# sensorHubRev7.net
KiCad netlist of a schematic drawn in EAGLE
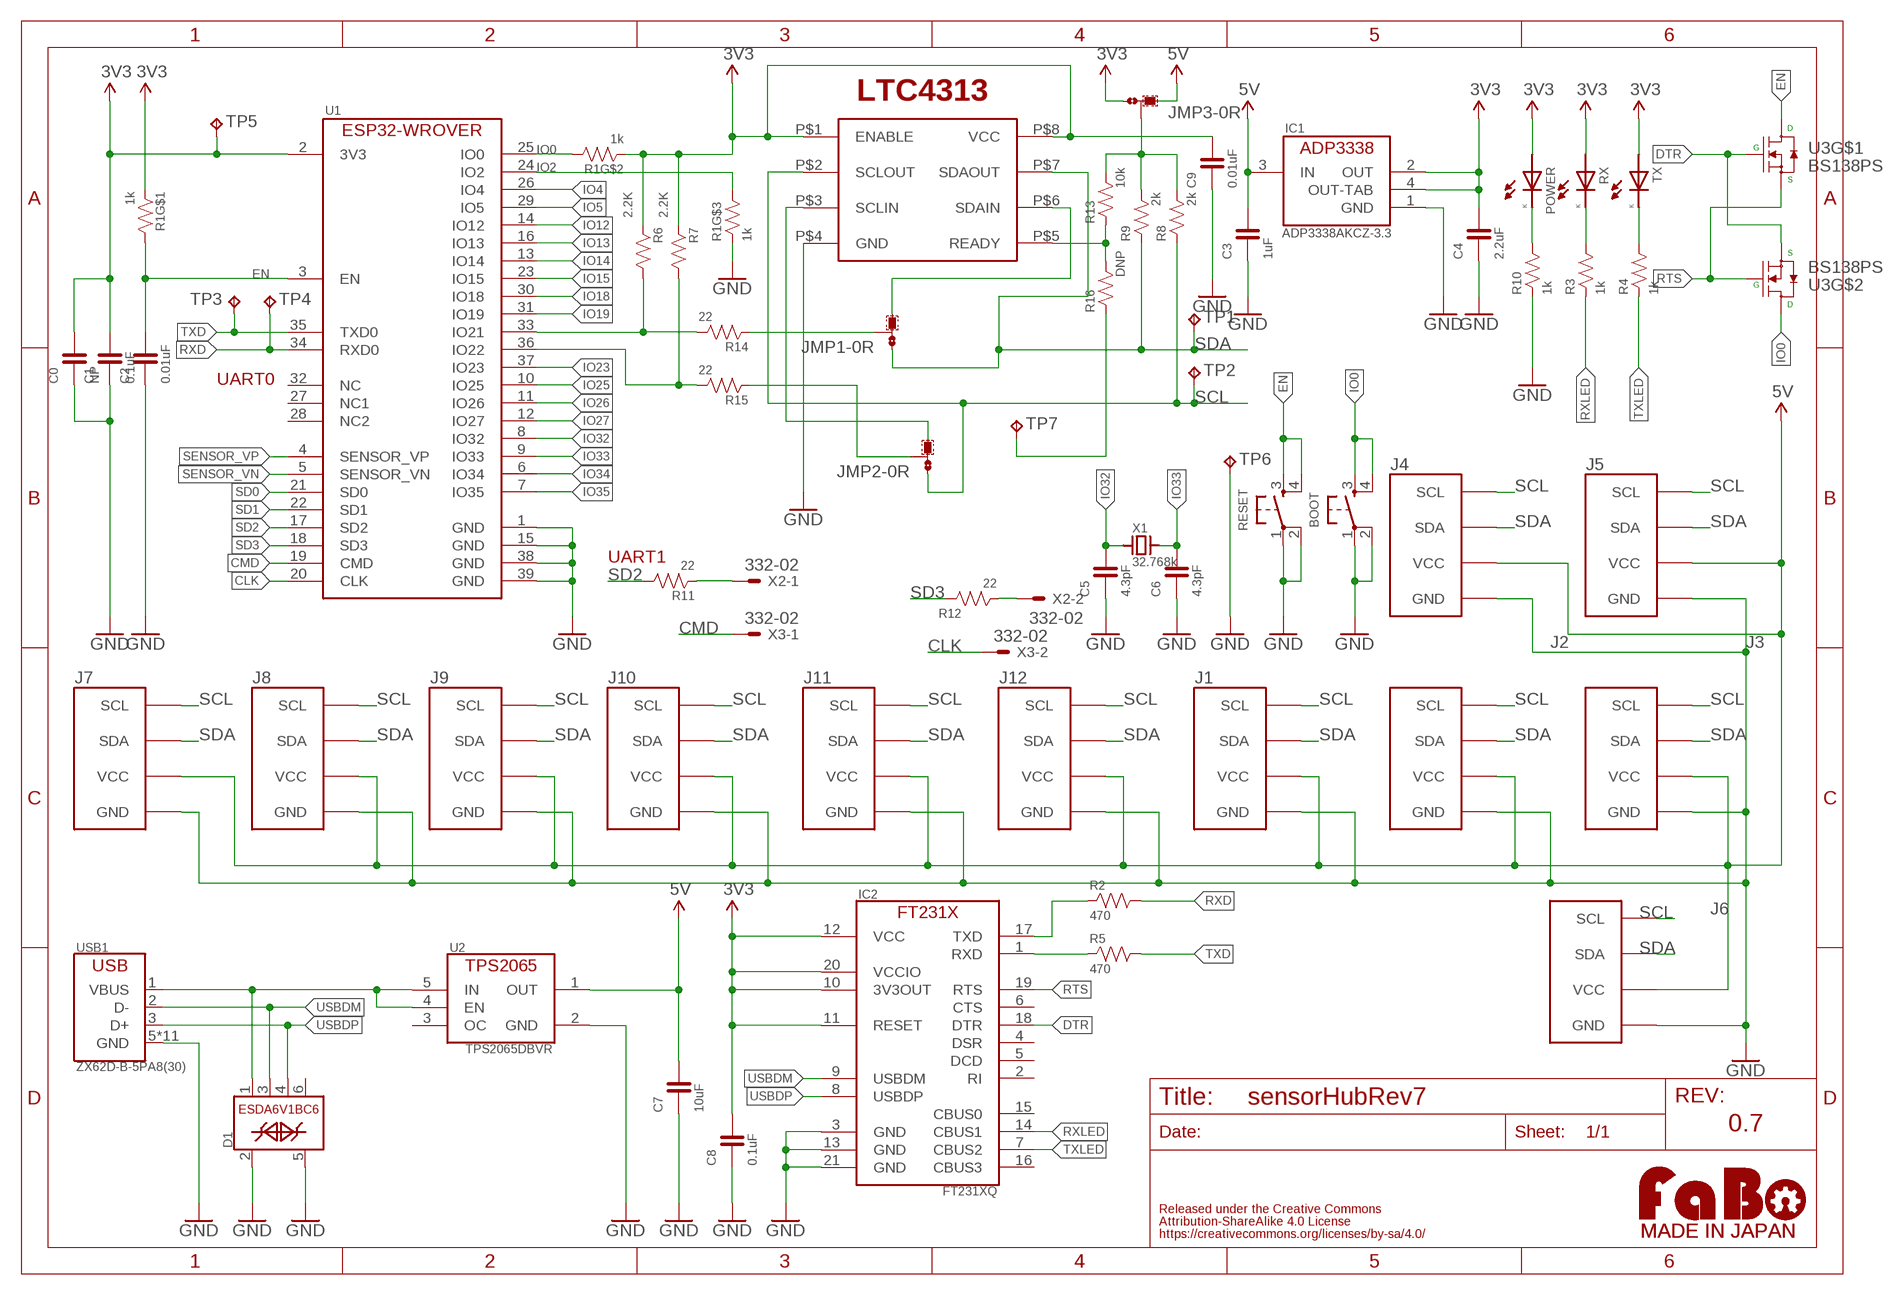
[diagram p0: schematic, sheet 1]

(export (version "E")
  (design (tool "Eeschema 10.0.6"))
  (components
    (comp (ref "BOOT")
      (value "TACTILE-KMR2")
      (footprint "eagle-import:KMR2-TACT")
      (libsource (lib "eagle-import") (part "TACTILE-KMR2"))
    )
    (comp (ref "C0")
      (value "NP")
      (footprint "eagle-import:MULTIPAD0603")
      (libsource (lib "eagle-import") (part "CAPACITOR-M"))
    )
    (comp (ref "C1")
      (value "0.1uF")
      (footprint "eagle-import:EIA0603")
      (libsource (lib "eagle-import") (part "CAPACITOR-0603"))
    )
    (comp (ref "C2")
      (value "0.01uF")
      (footprint "eagle-import:EIA0603")
      (libsource (lib "eagle-import") (part "CAPACITOR-0603"))
    )
    (comp (ref "C3")
      (value "1uF")
      (footprint "eagle-import:EIA0603")
      (libsource (lib "eagle-import") (part "CAPACITOR-0603"))
    )
    (comp (ref "C4")
      (value "2.2uF")
      (footprint "eagle-import:EIA0603")
      (libsource (lib "eagle-import") (part "CAPACITOR-0603"))
    )
    (comp (ref "C5")
      (value "4.3pF")
      (footprint "eagle-import:EIA0603")
      (libsource (lib "eagle-import") (part "CAPACITOR-0603"))
    )
    (comp (ref "C6")
      (value "4.3pF")
      (footprint "eagle-import:EIA0603")
      (libsource (lib "eagle-import") (part "CAPACITOR-0603"))
    )
    (comp (ref "C7")
      (value "10uF")
      (footprint "eagle-import:EIA0603")
      (libsource (lib "eagle-import") (part "CAPACITOR-0603"))
    )
    (comp (ref "C8")
      (value "0.1uF")
      (footprint "eagle-import:EIA0603")
      (libsource (lib "eagle-import") (part "CAPACITOR-0603"))
    )
    (comp (ref "C9")
      (value "0.01uF")
      (footprint "eagle-import:EIA0603")
      (libsource (lib "eagle-import") (part "CAPACITOR-0603"))
    )
    (comp (ref "D1")
      (value "ESDA6V1BC6")
      (footprint "eagle-import:SOT-23-6L")
      (libsource (lib "eagle-import") (part "ESDA6V1BC6"))
    )
    (comp (ref "IC1")
      (value "ADP3338AKCZ-3.3")
      (footprint "eagle-import:SOT-223-KC3")
      (libsource (lib "eagle-import") (part "ADP3338AKCZ"))
    )
    (comp (ref "IC2")
      (value "FT231XQ")
      (footprint "eagle-import:QFN-20")
      (libsource (lib "eagle-import") (part "FT231XQ"))
    )
    (comp (ref "J1")
      (value "FABO_BRICK_I2C-S04B-PASK-2")
      (footprint "eagle-import:FABO_BRICK_I2C_S04B-PASK-2")
      (libsource (lib "eagle-import") (part "FABO_BRICK_I2C-S04B-PASK-2"))
    )
    (comp (ref "J2")
      (value "FABO_BRICK_I2C-S04B-PASK-2")
      (footprint "eagle-import:FABO_BRICK_I2C_S04B-PASK-2")
      (libsource (lib "eagle-import") (part "FABO_BRICK_I2C-S04B-PASK-2"))
    )
    (comp (ref "J3")
      (value "FABO_BRICK_I2C-S04B-PASK-2")
      (footprint "eagle-import:FABO_BRICK_I2C_S04B-PASK-2")
      (libsource (lib "eagle-import") (part "FABO_BRICK_I2C-S04B-PASK-2"))
    )
    (comp (ref "J4")
      (value "FABO_BRICK_I2C-S04B-PASK-2")
      (footprint "eagle-import:FABO_BRICK_I2C_S04B-PASK-2")
      (libsource (lib "eagle-import") (part "FABO_BRICK_I2C-S04B-PASK-2"))
    )
    (comp (ref "J5")
      (value "FABO_BRICK_I2C-S04B-PASK-2")
      (footprint "eagle-import:FABO_BRICK_I2C_S04B-PASK-2")
      (libsource (lib "eagle-import") (part "FABO_BRICK_I2C-S04B-PASK-2"))
    )
    (comp (ref "J6")
      (value "FABO_BRICK_I2C-S04B-PASK-2")
      (footprint "eagle-import:FABO_BRICK_I2C_S04B-PASK-2")
      (libsource (lib "eagle-import") (part "FABO_BRICK_I2C-S04B-PASK-2"))
    )
    (comp (ref "J7")
      (value "FABO_BRICK_I2C-S04B-PASK-2")
      (footprint "eagle-import:FABO_BRICK_I2C_S04B-PASK-2")
      (libsource (lib "eagle-import") (part "FABO_BRICK_I2C-S04B-PASK-2"))
    )
    (comp (ref "J8")
      (value "FABO_BRICK_I2C-S04B-PASK-2")
      (footprint "eagle-import:FABO_BRICK_I2C_S04B-PASK-2")
      (libsource (lib "eagle-import") (part "FABO_BRICK_I2C-S04B-PASK-2"))
    )
    (comp (ref "J9")
      (value "FABO_BRICK_I2C-S04B-PASK-2")
      (footprint "eagle-import:FABO_BRICK_I2C_S04B-PASK-2")
      (libsource (lib "eagle-import") (part "FABO_BRICK_I2C-S04B-PASK-2"))
    )
    (comp (ref "J10")
      (value "FABO_BRICK_I2C-S04B-PASK-2")
      (footprint "eagle-import:FABO_BRICK_I2C_S04B-PASK-2")
      (libsource (lib "eagle-import") (part "FABO_BRICK_I2C-S04B-PASK-2"))
    )
    (comp (ref "J11")
      (value "FABO_BRICK_I2C-S04B-PASK-2")
      (footprint "eagle-import:FABO_BRICK_I2C_S04B-PASK-2")
      (libsource (lib "eagle-import") (part "FABO_BRICK_I2C-S04B-PASK-2"))
    )
    (comp (ref "J12")
      (value "FABO_BRICK_I2C-S04B-PASK-2")
      (footprint "eagle-import:FABO_BRICK_I2C_S04B-PASK-2")
      (libsource (lib "eagle-import") (part "FABO_BRICK_I2C-S04B-PASK-2"))
    )
    (comp (ref "JMP1")
      (value "0R-JUMPA")
      (footprint "eagle-import:A0R-JMP")
      (libsource (lib "eagle-import") (part "0R-JUMPA"))
    )
    (comp (ref "JMP2")
      (value "0R-JUMPA")
      (footprint "eagle-import:A0R-JMP")
      (libsource (lib "eagle-import") (part "0R-JUMPA"))
    )
    (comp (ref "JMP3")
      (value "0R-JUMPB")
      (footprint "eagle-import:B0R-JMP")
      (libsource (lib "eagle-import") (part "0R-JUMPB"))
    )
    (comp (ref "LOGO1")
      (value "LOGO_FABO-M_BOTTOM")
      (footprint "eagle-import:LOGO_FABO_M_BOTTOM")
      (libsource (lib "eagle-import") (part "LOGO_FABO-M_BOTTOM"))
    )
    (comp (ref "POWER")
      (value "LED-0603")
      (footprint "eagle-import:LED_0603")
      (libsource (lib "eagle-import") (part "LED-0603"))
    )
    (comp (ref "R1")
      (value "1k")
      (footprint "eagle-import:EXBV8V")
      (libsource (lib "eagle-import") (part "RESISTOR_ARRAY"))
    )
    (comp (ref "R2")
      (value "470")
      (footprint "eagle-import:EIA0603")
      (libsource (lib "eagle-import") (part "RESISTOR-0603"))
    )
    (comp (ref "R3")
      (value "1k")
      (footprint "eagle-import:EIA0603")
      (libsource (lib "eagle-import") (part "RESISTOR-0603"))
    )
    (comp (ref "R4")
      (value "1k")
      (footprint "eagle-import:EIA0603")
      (libsource (lib "eagle-import") (part "RESISTOR-0603"))
    )
    (comp (ref "R5")
      (value "470")
      (footprint "eagle-import:EIA0603")
      (libsource (lib "eagle-import") (part "RESISTOR-0603"))
    )
    (comp (ref "R6")
      (value "2.2K")
      (footprint "eagle-import:EIA0603")
      (libsource (lib "eagle-import") (part "RESISTOR-0603"))
    )
    (comp (ref "R7")
      (value "2.2K")
      (footprint "eagle-import:EIA0603")
      (libsource (lib "eagle-import") (part "RESISTOR-0603"))
    )
    (comp (ref "R8")
      (value "2k")
      (footprint "eagle-import:EIA0603")
      (libsource (lib "eagle-import") (part "RESISTOR-0603"))
    )
    (comp (ref "R9")
      (value "2k")
      (footprint "eagle-import:EIA0603")
      (libsource (lib "eagle-import") (part "RESISTOR-0603"))
    )
    (comp (ref "R10")
      (value "1k")
      (footprint "eagle-import:EIA0603")
      (libsource (lib "eagle-import") (part "RESISTOR-0603"))
    )
    (comp (ref "R11")
      (value "22")
      (footprint "eagle-import:EIA0603")
      (libsource (lib "eagle-import") (part "RESISTOR-0603"))
    )
    (comp (ref "R12")
      (value "22")
      (footprint "eagle-import:EIA0603")
      (libsource (lib "eagle-import") (part "RESISTOR-0603"))
    )
    (comp (ref "R13")
      (value "10k")
      (footprint "eagle-import:EIA0603")
      (libsource (lib "eagle-import") (part "RESISTOR-0603"))
    )
    (comp (ref "R14")
      (value "22")
      (footprint "eagle-import:EIA0603")
      (libsource (lib "eagle-import") (part "RESISTOR-0603"))
    )
    (comp (ref "R15")
      (value "22")
      (footprint "eagle-import:EIA0603")
      (libsource (lib "eagle-import") (part "RESISTOR-0603"))
    )
    (comp (ref "R16")
      (value "DNP")
      (footprint "eagle-import:EIA0603")
      (libsource (lib "eagle-import") (part "RESISTOR-0603"))
    )
    (comp (ref "RESET")
      (value "TACTILE-KMR2")
      (footprint "eagle-import:KMR2-TACT")
      (libsource (lib "eagle-import") (part "TACTILE-KMR2"))
    )
    (comp (ref "RX")
      (value "LED-0603")
      (footprint "eagle-import:LED_0603")
      (libsource (lib "eagle-import") (part "LED-0603"))
    )
    (comp (ref "TP1")
      (value "TPB1,27")
      (footprint "eagle-import:B1,27")
      (libsource (lib "eagle-import") (part "TPB1,27"))
    )
    (comp (ref "TP2")
      (value "TPB1,27")
      (footprint "eagle-import:B1,27")
      (libsource (lib "eagle-import") (part "TPB1,27"))
    )
    (comp (ref "TP3")
      (value "TPB1,27")
      (footprint "eagle-import:B1,27")
      (libsource (lib "eagle-import") (part "TPB1,27"))
    )
    (comp (ref "TP4")
      (value "TPB1,27")
      (footprint "eagle-import:B1,27")
      (libsource (lib "eagle-import") (part "TPB1,27"))
    )
    (comp (ref "TP5")
      (value "TPB1,27")
      (footprint "eagle-import:B1,27")
      (libsource (lib "eagle-import") (part "TPB1,27"))
    )
    (comp (ref "TP6")
      (value "TPB1,27")
      (footprint "eagle-import:B1,27")
      (libsource (lib "eagle-import") (part "TPB1,27"))
    )
    (comp (ref "TP7")
      (value "TPB1,27")
      (footprint "eagle-import:B1,27")
      (libsource (lib "eagle-import") (part "TPB1,27"))
    )
    (comp (ref "TX")
      (value "LED-0603")
      (footprint "eagle-import:LED_0603")
      (libsource (lib "eagle-import") (part "LED-0603"))
    )
    (comp (ref "U1")
      (value "ESP32-WROVER-B")
      (footprint "eagle-import:ESP32-WROVER-B")
      (libsource (lib "eagle-import") (part "ESP32-WROVER-B"))
    )
    (comp (ref "U2")
      (value "TPS2065DBVR")
      (footprint "eagle-import:SOT-23-5")
      (libsource (lib "eagle-import") (part "TPS2065DBV"))
    )
    (comp (ref "U3")
      (value "BS138PS")
      (footprint "eagle-import:SOT-363")
      (libsource (lib "eagle-import") (part "BS138PS"))
    )
    (comp (ref "U5")
      (value "LTC4313")
      (footprint "eagle-import:LTC4313")
      (libsource (lib "eagle-import") (part "LTC4313"))
    )
    (comp (ref "USB1")
      (value "ZX62D-B-5PA8(30)")
      (footprint "eagle-import:ZX62D-B-5PA8")
      (libsource (lib "eagle-import") (part "USB-ZX62D"))
    )
    (comp (ref "X1")
      (value "32.768k")
      (footprint "eagle-import:ABS07")
      (libsource (lib "eagle-import") (part "CRYSTAL-ABS07"))
    )
    (comp (ref "X2")
      (value "332-02")
      (footprint "eagle-import:332-02")
      (libsource (lib "eagle-import") (part "332-02"))
    )
    (comp (ref "X3")
      (value "332-02")
      (footprint "eagle-import:332-02")
      (libsource (lib "eagle-import") (part "332-02"))
    )
  )
  (nets
    (net (code "1") (name "/IO2") (class "Default")
      (node (ref "R1") (pin "6") (pinfunction "2_6") (pintype "bidirectional"))
      (node (ref "U1") (pin "24") (pinfunction "IO2_24") (pintype "bidirectional"))
    )
    (net (code "2") (name "/SCL") (class "Default")
      (node (ref "J1") (pin "SCL") (pinfunction "SCL_SCL") (pintype "bidirectional"))
      (node (ref "J10") (pin "SCL") (pinfunction "SCL_SCL") (pintype "bidirectional"))
      (node (ref "J11") (pin "SCL") (pinfunction "SCL_SCL") (pintype "bidirectional"))
      (node (ref "J12") (pin "SCL") (pinfunction "SCL_SCL") (pintype "bidirectional"))
      (node (ref "J2") (pin "SCL") (pinfunction "SCL_SCL") (pintype "bidirectional"))
      (node (ref "J3") (pin "SCL") (pinfunction "SCL_SCL") (pintype "bidirectional"))
      (node (ref "J4") (pin "SCL") (pinfunction "SCL_SCL") (pintype "bidirectional"))
      (node (ref "J5") (pin "SCL") (pinfunction "SCL_SCL") (pintype "bidirectional"))
      (node (ref "J6") (pin "SCL") (pinfunction "SCL_SCL") (pintype "bidirectional"))
      (node (ref "J7") (pin "SCL") (pinfunction "SCL_SCL") (pintype "bidirectional"))
      (node (ref "J8") (pin "SCL") (pinfunction "SCL_SCL") (pintype "bidirectional"))
      (node (ref "J9") (pin "SCL") (pinfunction "SCL_SCL") (pintype "bidirectional"))
      (node (ref "JMP2") (pin "1") (pinfunction "1_1") (pintype "passive"))
      (node (ref "R8") (pin "1") (pinfunction "1_1") (pintype "bidirectional"))
      (node (ref "TP2") (pin "TP") (pinfunction "TP_TP") (pintype "input"))
      (node (ref "U5") (pin "P$2") (pinfunction "SCLOUT_P$2") (pintype "bidirectional"))
    )
    (net (code "3") (name "/SDA") (class "Default")
      (node (ref "J1") (pin "SDA") (pinfunction "SDA_SDA") (pintype "bidirectional"))
      (node (ref "J10") (pin "SDA") (pinfunction "SDA_SDA") (pintype "bidirectional"))
      (node (ref "J11") (pin "SDA") (pinfunction "SDA_SDA") (pintype "bidirectional"))
      (node (ref "J12") (pin "SDA") (pinfunction "SDA_SDA") (pintype "bidirectional"))
      (node (ref "J2") (pin "SDA") (pinfunction "SDA_SDA") (pintype "bidirectional"))
      (node (ref "J3") (pin "SDA") (pinfunction "SDA_SDA") (pintype "bidirectional"))
      (node (ref "J4") (pin "SDA") (pinfunction "SDA_SDA") (pintype "bidirectional"))
      (node (ref "J5") (pin "SDA") (pinfunction "SDA_SDA") (pintype "bidirectional"))
      (node (ref "J6") (pin "SDA") (pinfunction "SDA_SDA") (pintype "bidirectional"))
      (node (ref "J7") (pin "SDA") (pinfunction "SDA_SDA") (pintype "bidirectional"))
      (node (ref "J8") (pin "SDA") (pinfunction "SDA_SDA") (pintype "bidirectional"))
      (node (ref "J9") (pin "SDA") (pinfunction "SDA_SDA") (pintype "bidirectional"))
      (node (ref "JMP1") (pin "1") (pinfunction "1_1") (pintype "passive"))
      (node (ref "R9") (pin "1") (pinfunction "1_1") (pintype "bidirectional"))
      (node (ref "TP1") (pin "TP") (pinfunction "TP_TP") (pintype "input"))
      (node (ref "U5") (pin "P$7") (pinfunction "SDAOUT_P$7") (pintype "bidirectional"))
    )
    (net (code "4") (name "3V3") (class "Default")
      (node (ref "C0") (pin "2") (pinfunction "2_2") (pintype "passive"))
      (node (ref "C1") (pin "2") (pinfunction "2_2") (pintype "passive"))
      (node (ref "C4") (pin "2") (pinfunction "2_2") (pintype "passive"))
      (node (ref "C8") (pin "2") (pinfunction "2_2") (pintype "passive"))
      (node (ref "C9") (pin "2") (pinfunction "2_2") (pintype "passive"))
      (node (ref "IC1") (pin "2") (pinfunction "OUT_2") (pintype "bidirectional"))
      (node (ref "IC1") (pin "4") (pinfunction "OUT-TAB_4") (pintype "bidirectional"))
      (node (ref "IC2") (pin "10") (pinfunction "3V3OUT_10") (pintype "bidirectional"))
      (node (ref "IC2") (pin "11") (pinfunction "RESET_11") (pintype "bidirectional"))
      (node (ref "IC2") (pin "12") (pinfunction "VCC_12") (pintype "bidirectional"))
      (node (ref "IC2") (pin "20") (pinfunction "VCCIO_20") (pintype "bidirectional"))
      (node (ref "JMP3") (pin "3") (pinfunction "3_3") (pintype "passive"))
      (node (ref "POWER") (pin "A") (pinfunction "ANODE_A") (pintype "passive"))
      (node (ref "R1") (pin "1") (pinfunction "1_1") (pintype "bidirectional"))
      (node (ref "R1") (pin "2") (pinfunction "1_2") (pintype "bidirectional"))
      (node (ref "R6") (pin "1") (pinfunction "1_1") (pintype "bidirectional"))
      (node (ref "R7") (pin "1") (pinfunction "1_1") (pintype "bidirectional"))
      (node (ref "RX") (pin "A") (pinfunction "ANODE_A") (pintype "passive"))
      (node (ref "TP5") (pin "TP") (pinfunction "TP_TP") (pintype "input"))
      (node (ref "TX") (pin "A") (pinfunction "ANODE_A") (pintype "passive"))
      (node (ref "U1") (pin "2") (pinfunction "3V3_2") (pintype "bidirectional"))
      (node (ref "U5") (pin "P$1") (pinfunction "ENABLE_P$1") (pintype "bidirectional"))
      (node (ref "U5") (pin "P$8") (pinfunction "VCC_P$8") (pintype "bidirectional"))
    )
    (net (code "5") (name "5V") (class "Default")
      (node (ref "C3") (pin "2") (pinfunction "2_2") (pintype "passive"))
      (node (ref "C7") (pin "2") (pinfunction "2_2") (pintype "passive"))
      (node (ref "IC1") (pin "3") (pinfunction "IN_3") (pintype "bidirectional"))
      (node (ref "J1") (pin "VCC") (pinfunction "VCC_VCC") (pintype "bidirectional"))
      (node (ref "J10") (pin "VCC") (pinfunction "VCC_VCC") (pintype "bidirectional"))
      (node (ref "J11") (pin "VCC") (pinfunction "VCC_VCC") (pintype "bidirectional"))
      (node (ref "J12") (pin "VCC") (pinfunction "VCC_VCC") (pintype "bidirectional"))
      (node (ref "J2") (pin "VCC") (pinfunction "VCC_VCC") (pintype "bidirectional"))
      (node (ref "J3") (pin "VCC") (pinfunction "VCC_VCC") (pintype "bidirectional"))
      (node (ref "J4") (pin "VCC") (pinfunction "VCC_VCC") (pintype "bidirectional"))
      (node (ref "J5") (pin "VCC") (pinfunction "VCC_VCC") (pintype "bidirectional"))
      (node (ref "J6") (pin "VCC") (pinfunction "VCC_VCC") (pintype "bidirectional"))
      (node (ref "J7") (pin "VCC") (pinfunction "VCC_VCC") (pintype "bidirectional"))
      (node (ref "J8") (pin "VCC") (pinfunction "VCC_VCC") (pintype "bidirectional"))
      (node (ref "J9") (pin "VCC") (pinfunction "VCC_VCC") (pintype "bidirectional"))
      (node (ref "JMP3") (pin "1") (pinfunction "1_1") (pintype "passive"))
      (node (ref "U2") (pin "1") (pinfunction "OUT_1") (pintype "bidirectional"))
    )
    (net (code "6") (name "CLK") (class "Default")
      (node (ref "U1") (pin "20") (pinfunction "CLK_20") (pintype "bidirectional"))
      (node (ref "X3") (pin "2") (pinfunction "S_2") (pintype "passive"))
    )
    (net (code "7") (name "CMD") (class "Default")
      (node (ref "U1") (pin "19") (pinfunction "CMD_19") (pintype "bidirectional"))
      (node (ref "X3") (pin "1") (pinfunction "S_1") (pintype "passive"))
    )
    (net (code "8") (name "DTR") (class "Default")
      (node (ref "IC2") (pin "18") (pinfunction "DTR_18") (pintype "bidirectional"))
      (node (ref "U3") (pin "2") (pinfunction "G_2") (pintype "passive"))
      (node (ref "U3") (pin "4") (pinfunction "S_4") (pintype "passive"))
    )
    (net (code "9") (name "EN") (class "Default")
      (node (ref "C2") (pin "2") (pinfunction "2_2") (pintype "passive"))
      (node (ref "R1") (pin "8") (pinfunction "2_8") (pintype "bidirectional"))
      (node (ref "RESET") (pin "3") (pinfunction "3_3") (pintype "passive"))
      (node (ref "RESET") (pin "4") (pinfunction "4_4") (pintype "passive"))
      (node (ref "U1") (pin "3") (pinfunction "EN_3") (pintype "bidirectional"))
      (node (ref "U3") (pin "6") (pinfunction "D_6") (pintype "passive"))
    )
    (net (code "10") (name "GND") (class "Default")
      (node (ref "BOOT") (pin "1") (pinfunction "1_1") (pintype "passive"))
      (node (ref "BOOT") (pin "2") (pinfunction "2_2") (pintype "passive"))
      (node (ref "C0") (pin "1") (pinfunction "1_1") (pintype "passive"))
      (node (ref "C1") (pin "1") (pinfunction "1_1") (pintype "passive"))
      (node (ref "C2") (pin "1") (pinfunction "1_1") (pintype "passive"))
      (node (ref "C3") (pin "1") (pinfunction "1_1") (pintype "passive"))
      (node (ref "C4") (pin "1") (pinfunction "1_1") (pintype "passive"))
      (node (ref "C5") (pin "1") (pinfunction "1_1") (pintype "passive"))
      (node (ref "C6") (pin "1") (pinfunction "1_1") (pintype "passive"))
      (node (ref "C7") (pin "1") (pinfunction "1_1") (pintype "passive"))
      (node (ref "C8") (pin "1") (pinfunction "1_1") (pintype "passive"))
      (node (ref "C9") (pin "1") (pinfunction "1_1") (pintype "passive"))
      (node (ref "D1") (pin "2") (pinfunction "2_2") (pintype "bidirectional"))
      (node (ref "D1") (pin "5") (pinfunction "5_5") (pintype "bidirectional"))
      (node (ref "IC1") (pin "1") (pinfunction "GND_1") (pintype "bidirectional"))
      (node (ref "IC2") (pin "13") (pinfunction "GND_13") (pintype "bidirectional"))
      (node (ref "IC2") (pin "21") (pinfunction "GND_21") (pintype "bidirectional"))
      (node (ref "IC2") (pin "3") (pinfunction "GND_3") (pintype "bidirectional"))
      (node (ref "J1") (pin "GND") (pinfunction "GND_GND") (pintype "bidirectional"))
      (node (ref "J10") (pin "GND") (pinfunction "GND_GND") (pintype "bidirectional"))
      (node (ref "J11") (pin "GND") (pinfunction "GND_GND") (pintype "bidirectional"))
      (node (ref "J12") (pin "GND") (pinfunction "GND_GND") (pintype "bidirectional"))
      (node (ref "J2") (pin "GND") (pinfunction "GND_GND") (pintype "bidirectional"))
      (node (ref "J3") (pin "GND") (pinfunction "GND_GND") (pintype "bidirectional"))
      (node (ref "J4") (pin "GND") (pinfunction "GND_GND") (pintype "bidirectional"))
      (node (ref "J5") (pin "GND") (pinfunction "GND_GND") (pintype "bidirectional"))
      (node (ref "J6") (pin "GND") (pinfunction "GND_GND") (pintype "bidirectional"))
      (node (ref "J7") (pin "GND") (pinfunction "GND_GND") (pintype "bidirectional"))
      (node (ref "J8") (pin "GND") (pinfunction "GND_GND") (pintype "bidirectional"))
      (node (ref "J9") (pin "GND") (pinfunction "GND_GND") (pintype "bidirectional"))
      (node (ref "R1") (pin "3") (pinfunction "1_3") (pintype "bidirectional"))
      (node (ref "R10") (pin "1") (pinfunction "1_1") (pintype "bidirectional"))
      (node (ref "RESET") (pin "1") (pinfunction "1_1") (pintype "passive"))
      (node (ref "RESET") (pin "2") (pinfunction "2_2") (pintype "passive"))
      (node (ref "TP6") (pin "TP") (pinfunction "TP_TP") (pintype "input"))
      (node (ref "U1") (pin "1") (pinfunction "GND_1") (pintype "bidirectional"))
      (node (ref "U1") (pin "15") (pinfunction "GND_15") (pintype "bidirectional"))
      (node (ref "U1") (pin "38") (pinfunction "GND_38") (pintype "bidirectional"))
      (node (ref "U1") (pin "39") (pinfunction "GND_39") (pintype "bidirectional"))
      (node (ref "U2") (pin "2") (pinfunction "GND_2") (pintype "bidirectional"))
      (node (ref "U5") (pin "P$4") (pinfunction "GND_P$4") (pintype "bidirectional"))
      (node (ref "USB1") (pin "5") (pinfunction "GND_5") (pintype "bidirectional"))
      (node (ref "USB1") (pin "B1") (pinfunction "GND_B1") (pintype "bidirectional"))
      (node (ref "USB1") (pin "B2") (pinfunction "GND_B2") (pintype "bidirectional"))
      (node (ref "USB1") (pin "B3") (pinfunction "GND_B3") (pintype "bidirectional"))
      (node (ref "USB1") (pin "B4") (pinfunction "GND_B4") (pintype "bidirectional"))
      (node (ref "USB1") (pin "T1") (pinfunction "GND_T1") (pintype "bidirectional"))
      (node (ref "USB1") (pin "T2") (pinfunction "GND_T2") (pintype "bidirectional"))
      (node (ref "USB1") (pin "T3") (pinfunction "GND_T3") (pintype "bidirectional"))
      (node (ref "USB1") (pin "T4") (pinfunction "GND_T4") (pintype "bidirectional"))
      (node (ref "USB1") (pin "T5") (pinfunction "GND_T5") (pintype "bidirectional"))
      (node (ref "USB1") (pin "T6") (pinfunction "GND_T6") (pintype "bidirectional"))
    )
    (net (code "11") (name "IO0") (class "Default")
      (node (ref "BOOT") (pin "3") (pinfunction "3_3") (pintype "passive"))
      (node (ref "BOOT") (pin "4") (pinfunction "4_4") (pintype "passive"))
      (node (ref "R1") (pin "7") (pinfunction "2_7") (pintype "bidirectional"))
      (node (ref "U1") (pin "25") (pinfunction "IO0_25") (pintype "bidirectional"))
      (node (ref "U3") (pin "3") (pinfunction "D_3") (pintype "passive"))
    )
    (net (code "12") (name "IO4") (class "Default")
      (node (ref "U1") (pin "26") (pinfunction "IO4_26") (pintype "bidirectional"))
    )
    (net (code "13") (name "IO5") (class "Default")
      (node (ref "U1") (pin "29") (pinfunction "IO5_29") (pintype "bidirectional"))
    )
    (net (code "14") (name "IO12") (class "Default")
      (node (ref "U1") (pin "14") (pinfunction "IO12_14") (pintype "bidirectional"))
    )
    (net (code "15") (name "IO13") (class "Default")
      (node (ref "U1") (pin "16") (pinfunction "IO13_16") (pintype "bidirectional"))
    )
    (net (code "16") (name "IO14") (class "Default")
      (node (ref "U1") (pin "13") (pinfunction "IO14_13") (pintype "bidirectional"))
    )
    (net (code "17") (name "IO15") (class "Default")
      (node (ref "U1") (pin "23") (pinfunction "IO15_23") (pintype "bidirectional"))
    )
    (net (code "18") (name "IO18") (class "Default")
      (node (ref "U1") (pin "30") (pinfunction "IO18_30") (pintype "bidirectional"))
    )
    (net (code "19") (name "IO19") (class "Default")
      (node (ref "U1") (pin "31") (pinfunction "IO19_31") (pintype "bidirectional"))
    )
    (net (code "20") (name "IO23") (class "Default")
      (node (ref "U1") (pin "37") (pinfunction "IO23_37") (pintype "bidirectional"))
    )
    (net (code "21") (name "IO25") (class "Default")
      (node (ref "U1") (pin "10") (pinfunction "IO25_10") (pintype "bidirectional"))
    )
    (net (code "22") (name "IO26") (class "Default")
      (node (ref "U1") (pin "11") (pinfunction "IO26_11") (pintype "bidirectional"))
    )
    (net (code "23") (name "IO27") (class "Default")
      (node (ref "U1") (pin "12") (pinfunction "IO27_12") (pintype "bidirectional"))
    )
    (net (code "24") (name "IO32") (class "Default")
      (node (ref "C5") (pin "2") (pinfunction "2_2") (pintype "passive"))
      (node (ref "U1") (pin "8") (pinfunction "IO32_8") (pintype "bidirectional"))
      (node (ref "X1") (pin "1") (pinfunction "P$1_1") (pintype "bidirectional"))
    )
    (net (code "25") (name "IO33") (class "Default")
      (node (ref "C6") (pin "2") (pinfunction "2_2") (pintype "passive"))
      (node (ref "U1") (pin "9") (pinfunction "IO33_9") (pintype "bidirectional"))
      (node (ref "X1") (pin "2") (pinfunction "P$2_2") (pintype "bidirectional"))
    )
    (net (code "26") (name "IO34") (class "Default")
      (node (ref "U1") (pin "6") (pinfunction "IO34_6") (pintype "bidirectional"))
    )
    (net (code "27") (name "IO35") (class "Default")
      (node (ref "U1") (pin "7") (pinfunction "IO35_7") (pintype "bidirectional"))
    )
    (net (code "28") (name "Net-(IC2-RXD)") (class "Default")
      (node (ref "IC2") (pin "1") (pinfunction "RXD_1") (pintype "bidirectional"))
      (node (ref "R5") (pin "1") (pinfunction "1_1") (pintype "bidirectional"))
    )
    (net (code "29") (name "Net-(IC2-TXD)") (class "Default")
      (node (ref "IC2") (pin "17") (pinfunction "TXD_17") (pintype "bidirectional"))
      (node (ref "R2") (pin "1") (pinfunction "1_1") (pintype "bidirectional"))
    )
    (net (code "30") (name "Net-(JMP1-Pad2)") (class "Default")
      (node (ref "JMP1") (pin "2") (pinfunction "2_2") (pintype "passive"))
      (node (ref "R14") (pin "1") (pinfunction "1_1") (pintype "bidirectional"))
    )
    (net (code "31") (name "Net-(JMP2-Pad2)") (class "Default")
      (node (ref "JMP2") (pin "2") (pinfunction "2_2") (pintype "passive"))
      (node (ref "R15") (pin "1") (pinfunction "1_1") (pintype "bidirectional"))
    )
    (net (code "32") (name "Net-(JMP3-Pad2)") (class "Default")
      (node (ref "JMP3") (pin "2") (pinfunction "2_2") (pintype "passive"))
      (node (ref "R13") (pin "2") (pinfunction "2_2") (pintype "bidirectional"))
      (node (ref "R8") (pin "2") (pinfunction "2_2") (pintype "bidirectional"))
      (node (ref "R9") (pin "2") (pinfunction "2_2") (pintype "bidirectional"))
    )
    (net (code "33") (name "Net-(POWER-CATHODE)") (class "Default")
      (node (ref "POWER") (pin "K") (pinfunction "CATHODE_K") (pintype "passive"))
      (node (ref "R10") (pin "2") (pinfunction "2_2") (pintype "bidirectional"))
    )
    (net (code "34") (name "Net-(R16-Pad1)") (class "Default")
      (node (ref "R16") (pin "1") (pinfunction "1_1") (pintype "bidirectional"))
      (node (ref "TP7") (pin "TP") (pinfunction "TP_TP") (pintype "input"))
    )
    (net (code "35") (name "Net-(RX-CATHODE)") (class "Default")
      (node (ref "R3") (pin "2") (pinfunction "2_2") (pintype "bidirectional"))
      (node (ref "RX") (pin "K") (pinfunction "CATHODE_K") (pintype "passive"))
    )
    (net (code "36") (name "Net-(TX-CATHODE)") (class "Default")
      (node (ref "R4") (pin "2") (pinfunction "2_2") (pintype "bidirectional"))
      (node (ref "TX") (pin "K") (pinfunction "CATHODE_K") (pintype "passive"))
    )
    (net (code "37") (name "Net-(U1-IO21)") (class "Default")
      (node (ref "R14") (pin "2") (pinfunction "2_2") (pintype "bidirectional"))
      (node (ref "R6") (pin "2") (pinfunction "2_2") (pintype "bidirectional"))
      (node (ref "U1") (pin "33") (pinfunction "IO21_33") (pintype "bidirectional"))
    )
    (net (code "38") (name "Net-(U1-IO22)") (class "Default")
      (node (ref "R15") (pin "2") (pinfunction "2_2") (pintype "bidirectional"))
      (node (ref "R7") (pin "2") (pinfunction "2_2") (pintype "bidirectional"))
      (node (ref "U1") (pin "36") (pinfunction "IO22_36") (pintype "bidirectional"))
    )
    (net (code "39") (name "Net-(U2-EN)") (class "Default")
      (node (ref "D1") (pin "1") (pinfunction "1_1") (pintype "bidirectional"))
      (node (ref "U2") (pin "4") (pinfunction "EN_4") (pintype "bidirectional"))
      (node (ref "U2") (pin "5") (pinfunction "IN_5") (pintype "bidirectional"))
      (node (ref "USB1") (pin "1") (pinfunction "VBUS_1") (pintype "bidirectional"))
    )
    (net (code "40") (name "Net-(U5-READY)") (class "Default")
      (node (ref "R13") (pin "1") (pinfunction "1_1") (pintype "bidirectional"))
      (node (ref "R16") (pin "2") (pinfunction "2_2") (pintype "bidirectional"))
      (node (ref "U5") (pin "P$5") (pinfunction "READY_P$5") (pintype "bidirectional"))
    )
    (net (code "41") (name "Net-(U5-SCLIN)") (class "Default")
      (node (ref "JMP2") (pin "3") (pinfunction "3_3") (pintype "passive"))
      (node (ref "U5") (pin "P$3") (pinfunction "SCLIN_P$3") (pintype "bidirectional"))
    )
    (net (code "42") (name "Net-(U5-SDAIN)") (class "Default")
      (node (ref "JMP1") (pin "3") (pinfunction "3_3") (pintype "passive"))
      (node (ref "U5") (pin "P$6") (pinfunction "SDAIN_P$6") (pintype "bidirectional"))
    )
    (net (code "43") (name "Net-(X2A-S)") (class "Default")
      (node (ref "R11") (pin "1") (pinfunction "1_1") (pintype "bidirectional"))
      (node (ref "X2") (pin "1") (pinfunction "S_1") (pintype "passive"))
    )
    (net (code "44") (name "Net-(X2B-S)") (class "Default")
      (node (ref "R12") (pin "1") (pinfunction "1_1") (pintype "bidirectional"))
      (node (ref "X2") (pin "2") (pinfunction "S_2") (pintype "passive"))
    )
    (net (code "45") (name "RTS") (class "Default")
      (node (ref "IC2") (pin "19") (pinfunction "RTS_19") (pintype "bidirectional"))
      (node (ref "U3") (pin "1") (pinfunction "S_1") (pintype "passive"))
      (node (ref "U3") (pin "5") (pinfunction "G_5") (pintype "passive"))
    )
    (net (code "46") (name "RXD") (class "Default")
      (node (ref "R2") (pin "2") (pinfunction "2_2") (pintype "bidirectional"))
      (node (ref "TP4") (pin "TP") (pinfunction "TP_TP") (pintype "input"))
      (node (ref "U1") (pin "34") (pinfunction "RXD0_34") (pintype "bidirectional"))
    )
    (net (code "47") (name "RXLED") (class "Default")
      (node (ref "IC2") (pin "14") (pinfunction "CBUS1_14") (pintype "bidirectional"))
      (node (ref "R3") (pin "1") (pinfunction "1_1") (pintype "bidirectional"))
    )
    (net (code "48") (name "SD0") (class "Default")
      (node (ref "U1") (pin "21") (pinfunction "SD0_21") (pintype "bidirectional"))
    )
    (net (code "49") (name "SD1") (class "Default")
      (node (ref "U1") (pin "22") (pinfunction "SD1_22") (pintype "bidirectional"))
    )
    (net (code "50") (name "SD2") (class "Default")
      (node (ref "R11") (pin "2") (pinfunction "2_2") (pintype "bidirectional"))
      (node (ref "U1") (pin "17") (pinfunction "SD2_17") (pintype "bidirectional"))
    )
    (net (code "51") (name "SD3") (class "Default")
      (node (ref "R12") (pin "2") (pinfunction "2_2") (pintype "bidirectional"))
      (node (ref "U1") (pin "18") (pinfunction "SD3_18") (pintype "bidirectional"))
    )
    (net (code "52") (name "SENSOR_VN") (class "Default")
      (node (ref "U1") (pin "5") (pinfunction "SENSOR_VN_5") (pintype "bidirectional"))
    )
    (net (code "53") (name "SENSOR_VP") (class "Default")
      (node (ref "U1") (pin "4") (pinfunction "SENSOR_VP_4") (pintype "bidirectional"))
    )
    (net (code "54") (name "TXD") (class "Default")
      (node (ref "R5") (pin "2") (pinfunction "2_2") (pintype "bidirectional"))
      (node (ref "TP3") (pin "TP") (pinfunction "TP_TP") (pintype "input"))
      (node (ref "U1") (pin "35") (pinfunction "TXD0_35") (pintype "bidirectional"))
    )
    (net (code "55") (name "TXLED") (class "Default")
      (node (ref "IC2") (pin "7") (pinfunction "CBUS2_7") (pintype "bidirectional"))
      (node (ref "R4") (pin "1") (pinfunction "1_1") (pintype "bidirectional"))
    )
    (net (code "56") (name "USBDM") (class "Default")
      (node (ref "D1") (pin "3") (pinfunction "3_3") (pintype "bidirectional"))
      (node (ref "IC2") (pin "9") (pinfunction "USBDM_9") (pintype "bidirectional"))
      (node (ref "USB1") (pin "2") (pinfunction "D-_2") (pintype "bidirectional"))
    )
    (net (code "57") (name "USBDP") (class "Default")
      (node (ref "D1") (pin "4") (pinfunction "4_4") (pintype "bidirectional"))
      (node (ref "IC2") (pin "8") (pinfunction "USBDP_8") (pintype "bidirectional"))
      (node (ref "USB1") (pin "3") (pinfunction "D+_3") (pintype "bidirectional"))
    )
    (net (code "58") (name "unconnected-(D1-Pad6)") (class "Default")
      (node (ref "D1") (pin "6") (pinfunction "6_6") (pintype "bidirectional"))
    )
    (net (code "59") (name "unconnected-(IC2-CBUS0-Pad15)") (class "Default")
      (node (ref "IC2") (pin "15") (pinfunction "CBUS0_15") (pintype "bidirectional"))
    )
    (net (code "60") (name "unconnected-(IC2-CBUS3-Pad16)") (class "Default")
      (node (ref "IC2") (pin "16") (pinfunction "CBUS3_16") (pintype "bidirectional"))
    )
    (net (code "61") (name "unconnected-(IC2-CTS-Pad6)") (class "Default")
      (node (ref "IC2") (pin "6") (pinfunction "CTS_6") (pintype "bidirectional"))
    )
    (net (code "62") (name "unconnected-(IC2-DCD-Pad5)") (class "Default")
      (node (ref "IC2") (pin "5") (pinfunction "DCD_5") (pintype "bidirectional"))
    )
    (net (code "63") (name "unconnected-(IC2-DSR-Pad4)") (class "Default")
      (node (ref "IC2") (pin "4") (pinfunction "DSR_4") (pintype "bidirectional"))
    )
    (net (code "64") (name "unconnected-(IC2-RI-Pad2)") (class "Default")
      (node (ref "IC2") (pin "2") (pinfunction "RI_2") (pintype "bidirectional"))
    )
    (net (code "65") (name "unconnected-(U1-NC-Pad32)") (class "Default")
      (node (ref "U1") (pin "32") (pinfunction "NC_32") (pintype "bidirectional"))
    )
    (net (code "66") (name "unconnected-(U1-NC1-Pad27)") (class "Default")
      (node (ref "U1") (pin "27") (pinfunction "NC1_27") (pintype "bidirectional"))
    )
    (net (code "67") (name "unconnected-(U1-NC2-Pad28)") (class "Default")
      (node (ref "U1") (pin "28") (pinfunction "NC2_28") (pintype "bidirectional"))
    )
    (net (code "68") (name "unconnected-(U2-OC-Pad3)") (class "Default")
      (node (ref "U2") (pin "3") (pinfunction "OC_3") (pintype "bidirectional"))
    )
  )
)
